# 555_Oscillator_Practice_Board.net
KiCad netlist of a schematic drawn in EAGLE
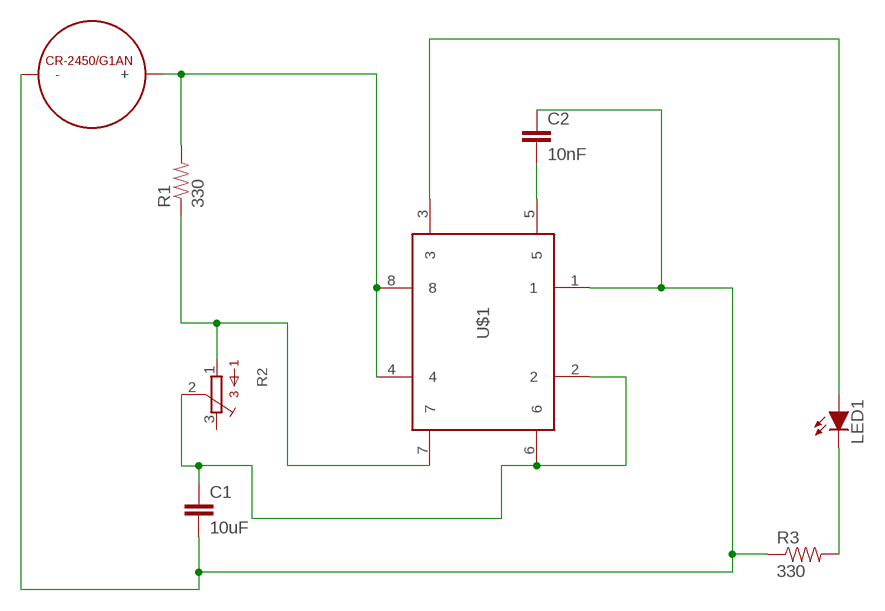
[diagram p0: schematic, sheet 1]

(export (version "E")
  (design (tool "Eeschema 10.0.6"))
  (components
    (comp (ref "C1")
      (value "10uF")
      (footprint "eagle-import:AXIAL-5MM")
      (libsource (lib "eagle-import") (part "CAP_"))
    )
    (comp (ref "C2")
      (value "10nF")
      (footprint "eagle-import:AXIAL-5MM")
      (libsource (lib "eagle-import") (part "CAP_"))
    )
    (comp (ref "LED1")
      (value "LED-5MM")
      (footprint "eagle-import:LED-5MM")
      (libsource (lib "eagle-import") (part "LED-5MM"))
    )
    (comp (ref "R1")
      (value "330")
      (footprint "eagle-import:AXIAL-0.3")
      (libsource (lib "eagle-import") (part "RESISTORAXIAL-0.3"))
    )
    (comp (ref "R2")
      (value "TRIMPOT_3296C")
      (footprint "eagle-import:TRIMPOT_3296")
      (libsource (lib "eagle-import") (part "TRIMPOT_3296C"))
    )
    (comp (ref "R3")
      (value "330")
      (footprint "eagle-import:AXIAL-0.3")
      (libsource (lib "eagle-import") (part "RESISTORAXIAL-0.3"))
    )
    (comp (ref "U$1")
      (value "555_TIMER")
      (footprint "eagle-import:DIL08")
      (libsource (lib "eagle-import") (part "555_TIMER"))
    )
    (comp (ref "U$2")
      (value "CR-2450/G1AN")
      (footprint "eagle-import:CR-2450_G1AN")
      (libsource (lib "eagle-import") (part "CR-2450/G1AN"))
    )
  )
  (nets
    (net (code "1") (name "Net-(C1-1)") (class "Default")
      (node (ref "C1") (pin "P$1") (pinfunction "1_P$1") (pintype "passive"))
      (node (ref "R2") (pin "2") (pinfunction "2_2") (pintype "passive"))
      (node (ref "U$1") (pin "2") (pinfunction "2_2") (pintype "bidirectional"))
      (node (ref "U$1") (pin "6") (pinfunction "6_6") (pintype "bidirectional"))
    )
    (net (code "2") (name "Net-(C1-2)") (class "Default")
      (node (ref "C1") (pin "P$2") (pinfunction "2_P$2") (pintype "passive"))
      (node (ref "C2") (pin "P$1") (pinfunction "1_P$1") (pintype "passive"))
      (node (ref "R3") (pin "P$1") (pinfunction "1_P$1") (pintype "passive"))
      (node (ref "U$1") (pin "1") (pinfunction "1_1") (pintype "bidirectional"))
      (node (ref "U$2") (pin "-") (pinfunction "-_-") (pintype "bidirectional"))
    )
    (net (code "3") (name "Net-(C2-2)") (class "Default")
      (node (ref "C2") (pin "P$2") (pinfunction "2_P$2") (pintype "passive"))
      (node (ref "U$1") (pin "5") (pinfunction "5_5") (pintype "bidirectional"))
    )
    (net (code "4") (name "Net-(LED1-C)") (class "Default")
      (node (ref "LED1") (pin "K") (pinfunction "C_K") (pintype "passive"))
      (node (ref "R3") (pin "P$2") (pinfunction "2_P$2") (pintype "passive"))
    )
    (net (code "5") (name "Net-(LED1-PadA)") (class "Default")
      (node (ref "LED1") (pin "A") (pinfunction "A_A") (pintype "passive"))
      (node (ref "U$1") (pin "3") (pinfunction "3_3") (pintype "bidirectional"))
    )
    (net (code "6") (name "Net-(R1-1)") (class "Default")
      (node (ref "R1") (pin "P$1") (pinfunction "1_P$1") (pintype "passive"))
      (node (ref "R2") (pin "1") (pinfunction "1_1") (pintype "passive"))
      (node (ref "U$1") (pin "7") (pinfunction "7_7") (pintype "bidirectional"))
    )
    (net (code "7") (name "Net-(R1-2)") (class "Default")
      (node (ref "R1") (pin "P$2") (pinfunction "2_P$2") (pintype "passive"))
      (node (ref "U$1") (pin "4") (pinfunction "4_4") (pintype "bidirectional"))
      (node (ref "U$1") (pin "8") (pinfunction "8_8") (pintype "bidirectional"))
      (node (ref "U$2") (pin "+_0") (pinfunction "+_+_0") (pintype "bidirectional"))
      (node (ref "U$2") (pin "+_1") (pinfunction "+_+_1") (pintype "bidirectional"))
    )
    (net (code "8") (name "unconnected-(R2-Pad3)") (class "Default")
      (node (ref "R2") (pin "3") (pinfunction "3_3") (pintype "passive"))
    )
  )
)
